# Whey_AGR_Sch.net
KiCad netlist of a schematic drawn in Altium Designer
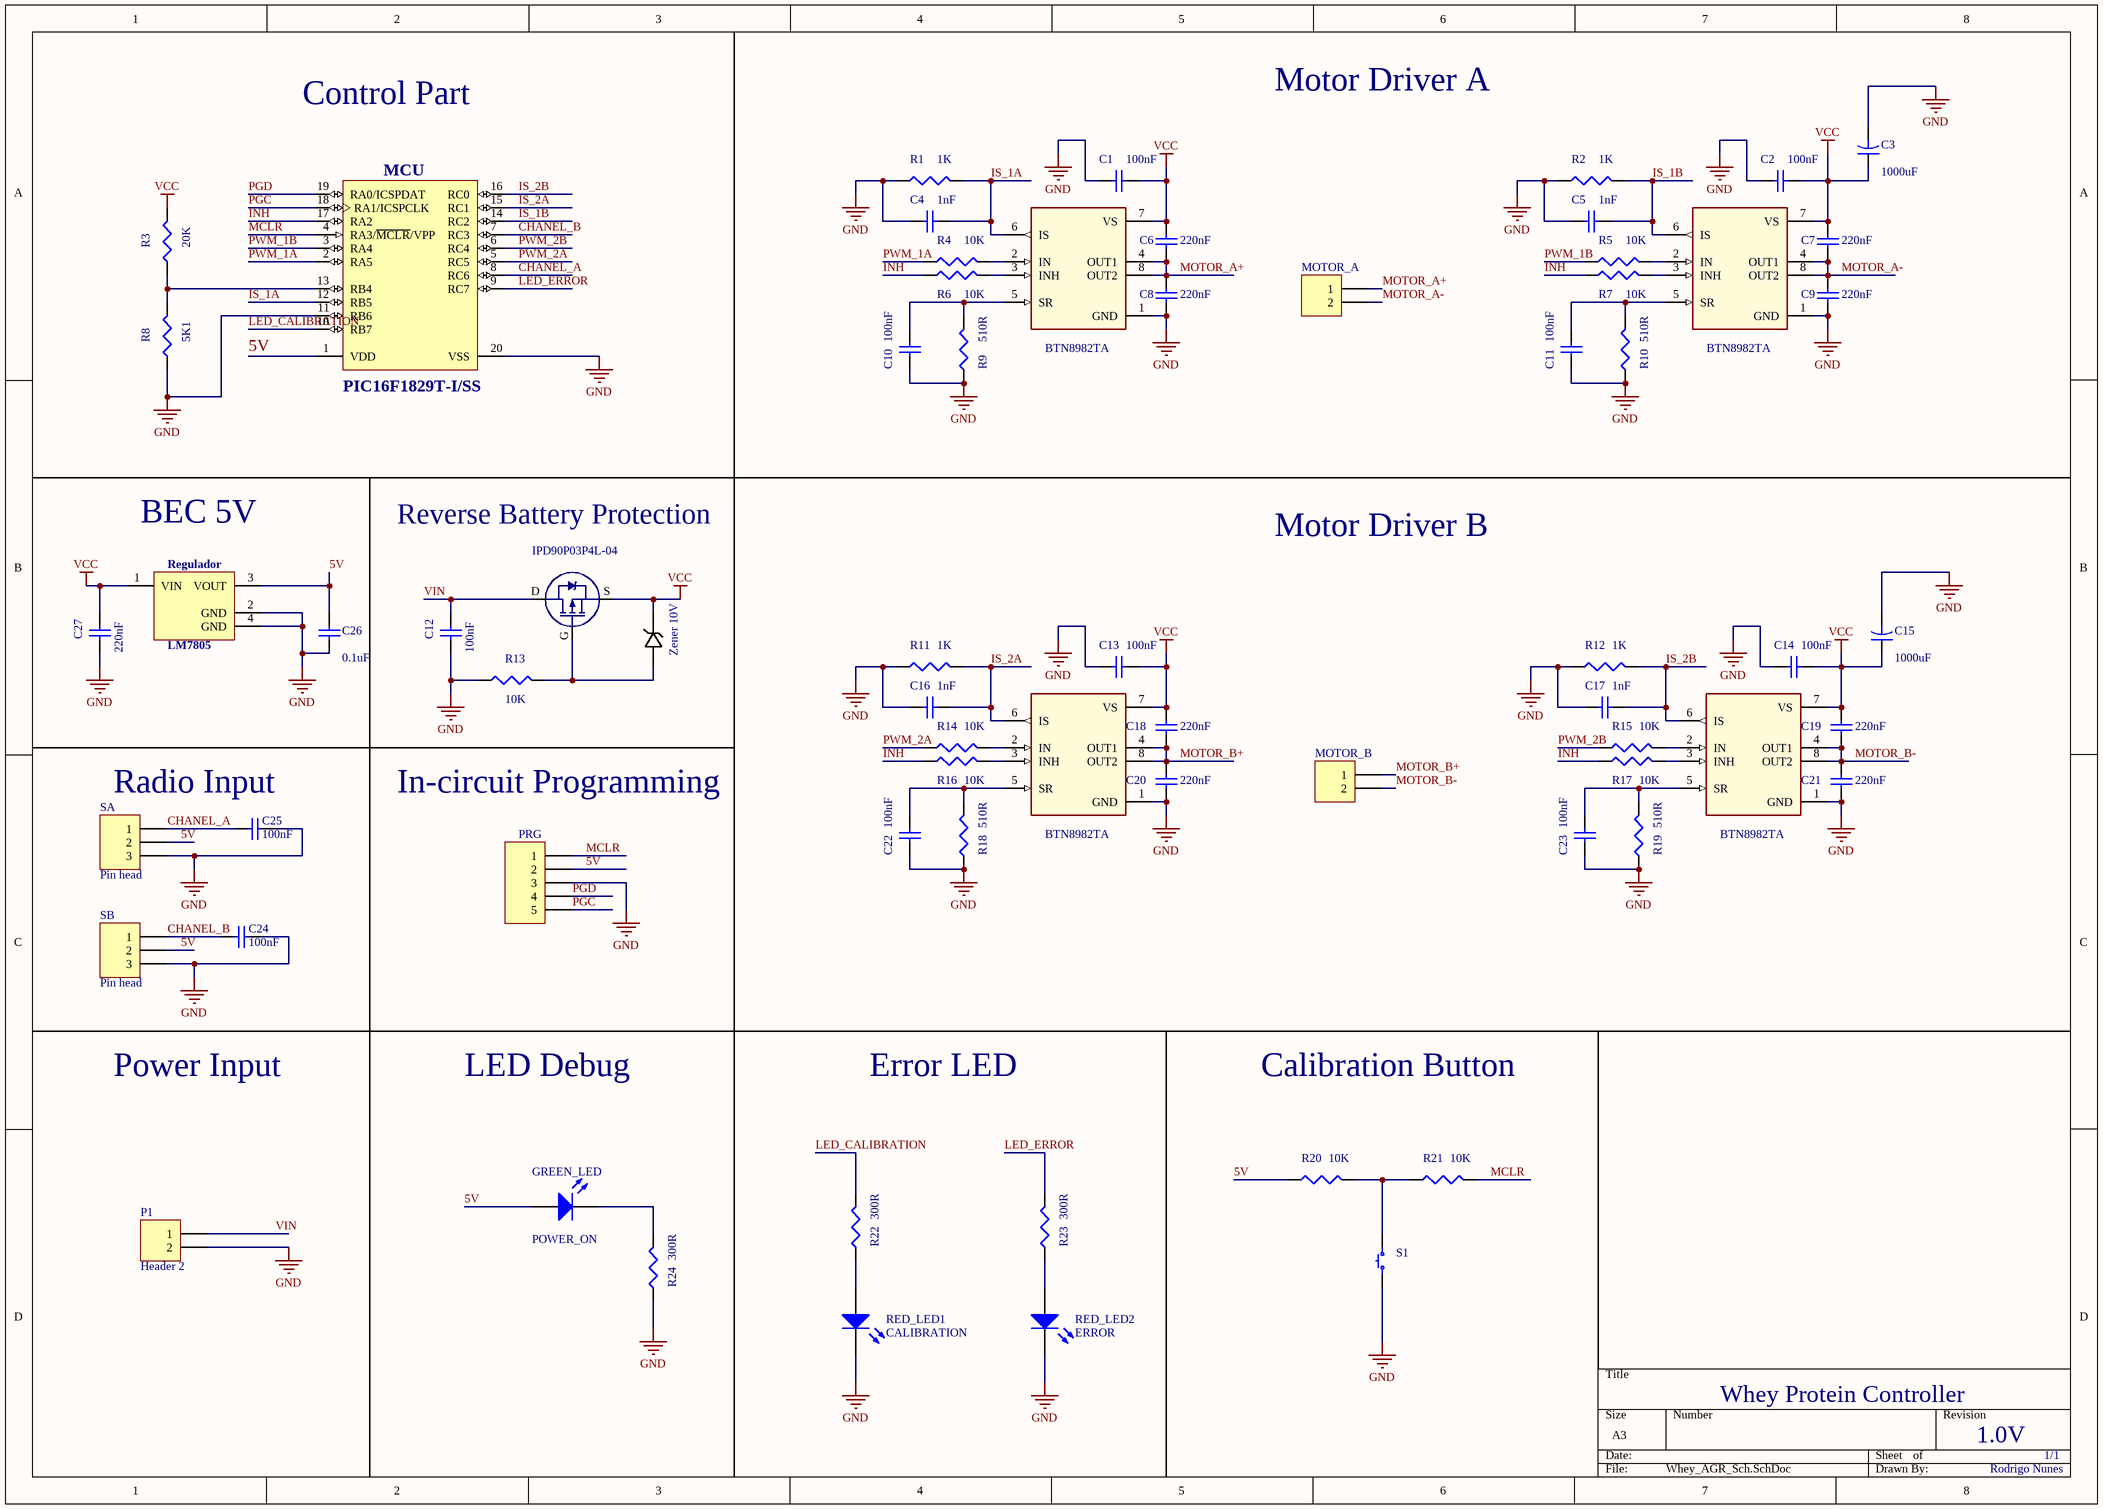
[diagram p0: Whey_AGR_Sch.SchDoc]

(export (version "E")
  (design (tool "Eeschema 10.0.6"))
  (components
    (comp (ref "C1")
      (value "100nF")
      (footprint "C1206")
      (description "Capacitor (Semiconductor SIM Model)")
      (fields (field (name "Comment") "Cap Semi") (field (name "PUBLISHER") "Altium Limited"))
      (libsource (lib "Miscellaneous Devices") (part "Cap Semi"))
    )
    (comp (ref "C2")
      (value "100nF")
      (footprint "C1206")
      (description "Capacitor (Semiconductor SIM Model)")
      (fields (field (name "Comment") "Cap Semi") (field (name "PUBLISHER") "Altium Limited"))
      (libsource (lib "Miscellaneous Devices") (part "Cap Semi"))
    )
    (comp (ref "C3")
      (value "1000uF")
      (footprint "CAPR5-4X5")
      (description "Capacitor")
      (fields (field (name "PUBLISHER") "Altium Limited"))
      (libsource (lib "Miscellaneous Devices") (part "Cap2"))
    )
    (comp (ref "C4")
      (value "1nF")
      (footprint "C1206")
      (description "Capacitor (Semiconductor SIM Model)")
      (fields (field (name "Comment") "Cap Semi") (field (name "PUBLISHER") "Altium Limited"))
      (libsource (lib "Miscellaneous Devices") (part "Cap Semi"))
    )
    (comp (ref "C5")
      (value "1nF")
      (footprint "C1206")
      (description "Capacitor (Semiconductor SIM Model)")
      (fields (field (name "Comment") "Cap Semi") (field (name "PUBLISHER") "Altium Limited"))
      (libsource (lib "Miscellaneous Devices") (part "Cap Semi"))
    )
    (comp (ref "C6")
      (value "220nF")
      (footprint "C1206")
      (description "Capacitor (Semiconductor SIM Model)")
      (fields (field (name "Comment") "Cap Semi") (field (name "PUBLISHER") "Altium Limited"))
      (libsource (lib "Miscellaneous Devices") (part "Cap Semi"))
    )
    (comp (ref "C7")
      (value "220nF")
      (footprint "C1206")
      (description "Capacitor (Semiconductor SIM Model)")
      (fields (field (name "Comment") "Cap Semi") (field (name "PUBLISHER") "Altium Limited"))
      (libsource (lib "Miscellaneous Devices") (part "Cap Semi"))
    )
    (comp (ref "C8")
      (value "220nF")
      (footprint "C1206")
      (description "Capacitor (Semiconductor SIM Model)")
      (fields (field (name "Comment") "Cap Semi") (field (name "PUBLISHER") "Altium Limited"))
      (libsource (lib "Miscellaneous Devices") (part "Cap Semi"))
    )
    (comp (ref "C9")
      (value "220nF")
      (footprint "C1206")
      (description "Capacitor (Semiconductor SIM Model)")
      (fields (field (name "Comment") "Cap Semi") (field (name "PUBLISHER") "Altium Limited"))
      (libsource (lib "Miscellaneous Devices") (part "Cap Semi"))
    )
    (comp (ref "C10")
      (value "100nF")
      (footprint "C1206")
      (description "Capacitor (Semiconductor SIM Model)")
      (fields (field (name "Comment") "Cap Semi") (field (name "PUBLISHER") "Altium Limited"))
      (libsource (lib "Miscellaneous Devices") (part "Cap Semi"))
    )
    (comp (ref "C11")
      (value "100nF")
      (footprint "C1206")
      (description "Capacitor (Semiconductor SIM Model)")
      (fields (field (name "Comment") "Cap Semi") (field (name "PUBLISHER") "Altium Limited"))
      (libsource (lib "Miscellaneous Devices") (part "Cap Semi"))
    )
    (comp (ref "C12")
      (value "100nF")
      (footprint "C1206")
      (description "Capacitor (Semiconductor SIM Model)")
      (fields (field (name "Comment") "Cap Semi") (field (name "PUBLISHER") "Altium Limited"))
      (libsource (lib "Miscellaneous Devices") (part "Cap Semi"))
    )
    (comp (ref "C13")
      (value "100nF")
      (footprint "C1206")
      (description "Capacitor (Semiconductor SIM Model)")
      (fields (field (name "Comment") "Cap Semi") (field (name "PUBLISHER") "Altium Limited"))
      (libsource (lib "Miscellaneous Devices") (part "Cap Semi"))
    )
    (comp (ref "C14")
      (value "100nF")
      (footprint "C1206")
      (description "Capacitor (Semiconductor SIM Model)")
      (fields (field (name "Comment") "Cap Semi") (field (name "PUBLISHER") "Altium Limited"))
      (libsource (lib "Miscellaneous Devices") (part "Cap Semi"))
    )
    (comp (ref "C15")
      (value "1000uF")
      (footprint "CAPR5-4X5")
      (description "Capacitor")
      (fields (field (name "Comment") "Cap2") (field (name "PUBLISHER") "Altium Limited"))
      (libsource (lib "Miscellaneous Devices") (part "Cap2"))
    )
    (comp (ref "C16")
      (value "1nF")
      (footprint "C1206")
      (description "Capacitor (Semiconductor SIM Model)")
      (fields (field (name "Comment") "Cap Semi") (field (name "PUBLISHER") "Altium Limited"))
      (libsource (lib "Miscellaneous Devices") (part "Cap Semi"))
    )
    (comp (ref "C17")
      (value "1nF")
      (footprint "C1206")
      (description "Capacitor (Semiconductor SIM Model)")
      (fields (field (name "Comment") "Cap Semi") (field (name "PUBLISHER") "Altium Limited"))
      (libsource (lib "Miscellaneous Devices") (part "Cap Semi"))
    )
    (comp (ref "C18")
      (value "220nF")
      (footprint "C1206")
      (description "Capacitor (Semiconductor SIM Model)")
      (fields (field (name "Comment") "Cap Semi") (field (name "PUBLISHER") "Altium Limited"))
      (libsource (lib "Miscellaneous Devices") (part "Cap Semi"))
    )
    (comp (ref "C19")
      (value "220nF")
      (footprint "C1206")
      (description "Capacitor (Semiconductor SIM Model)")
      (fields (field (name "Comment") "Cap Semi") (field (name "PUBLISHER") "Altium Limited"))
      (libsource (lib "Miscellaneous Devices") (part "Cap Semi"))
    )
    (comp (ref "C20")
      (value "220nF")
      (footprint "C1206")
      (description "Capacitor (Semiconductor SIM Model)")
      (fields (field (name "Comment") "Cap Semi") (field (name "PUBLISHER") "Altium Limited"))
      (libsource (lib "Miscellaneous Devices") (part "Cap Semi"))
    )
    (comp (ref "C21")
      (value "220nF")
      (footprint "C1206")
      (description "Capacitor (Semiconductor SIM Model)")
      (fields (field (name "Comment") "Cap Semi") (field (name "PUBLISHER") "Altium Limited"))
      (libsource (lib "Miscellaneous Devices") (part "Cap Semi"))
    )
    (comp (ref "C22")
      (value "100nF")
      (footprint "C1206")
      (description "Capacitor (Semiconductor SIM Model)")
      (fields (field (name "Comment") "Cap Semi") (field (name "PUBLISHER") "Altium Limited"))
      (libsource (lib "Miscellaneous Devices") (part "Cap Semi"))
    )
    (comp (ref "C23")
      (value "100nF")
      (footprint "C1206")
      (description "Capacitor (Semiconductor SIM Model)")
      (fields (field (name "Comment") "Cap Semi") (field (name "PUBLISHER") "Altium Limited"))
      (libsource (lib "Miscellaneous Devices") (part "Cap Semi"))
    )
    (comp (ref "C24")
      (value "100nF")
      (footprint "C1206")
      (description "Capacitor (Semiconductor SIM Model)")
      (fields (field (name "Comment") "Cap Semi") (field (name "PUBLISHER") "Altium Limited"))
      (libsource (lib "Miscellaneous Devices") (part "Cap Semi"))
    )
    (comp (ref "C25")
      (value "100nF")
      (footprint "C1206")
      (description "Capacitor (Semiconductor SIM Model)")
      (fields (field (name "Comment") "Cap Semi") (field (name "PUBLISHER") "Altium Limited"))
      (libsource (lib "Miscellaneous Devices") (part "Cap Semi"))
    )
    (comp (ref "C26")
      (value "0.1uF")
      (footprint "C1206")
      (description "Capacitor (Semiconductor SIM Model)")
      (fields (field (name "PUBLISHER") "Altium Limited"))
      (libsource (lib "Miscellaneous Devices") (part "Cap Semi"))
    )
    (comp (ref "C27")
      (value "220nF")
      (footprint "C1206")
      (description "Capacitor (Semiconductor SIM Model)")
      (fields (field (name "Comment") "Cap Semi") (field (name "PUBLISHER") "Altium Limited"))
      (libsource (lib "Miscellaneous Devices") (part "Cap Semi"))
    )
    (comp (ref "GREEN_LED")
      (value "POWER_ON")
      (footprint "3.2X1.6X1.1")
      (description "Typical RED, GREEN, YELLOW, AMBER GaAs LED")
      (fields (field (name "PUBLISHER") "Altium Limited"))
      (libsource (lib "Miscellaneous Devices") (part "LED2"))
    )
    (comp (ref "IPD90P03P4L-04")
      (value "IPD50P04P4")
      (footprint "TO-252")
      (description "MOSFET P-Ch -40V -50A DPAK-2 OptiMOS-P2")
      (libsource (lib "Components") (part "IPD50P04P4"))
    )
    (comp (ref "MCU")
      (value "PIC16F1829T-I/SS")
      (footprint "MCHP-SSOP-SS20_N")
      (fields (field (name "MANUFACTURER") "Microchip"))
      (libsource (lib "Microchip PIC16 Part 1") (part "PIC16F1829T-I/SS"))
    )
    (comp (ref "MOTOR_A")
      (value "Header 2")
      (footprint "HDR1X2")
      (description "Header, 2-Pin")
      (fields (field (name "PUBLISHER") "Altium Limited"))
      (libsource (lib "Miscellaneous Connectors") (part "Header 2"))
    )
    (comp (ref "MOTOR_B")
      (value "Header 2")
      (footprint "HDR1X2")
      (description "Header, 2-Pin")
      (fields (field (name "PUBLISHER") "Altium Limited"))
      (libsource (lib "Miscellaneous Connectors") (part "Header 2"))
    )
    (comp (ref "P1")
      (value "Header 2")
      (footprint "HDR1X2")
      (description "Header, 2-Pin")
      (fields (field (name "PUBLISHER") "Altium Limited"))
      (libsource (lib "Miscellaneous Connectors") (part "Header 2"))
    )
    (comp (ref "PRG")
      (value "Header 5")
      (footprint "HDR1X5")
      (description "Header, 5-Pin")
      (fields (field (name "PUBLISHER") "Altium Limited"))
      (libsource (lib "Miscellaneous Connectors") (part "Header 5"))
    )
    (comp (ref "R1")
      (value "1K")
      (footprint "J1-0603")
      (description "Resistor")
      (fields (field (name "Comment") "Res3") (field (name "PUBLISHER") "Altium Limited"))
      (libsource (lib "Miscellaneous Devices") (part "Res3"))
    )
    (comp (ref "R2")
      (value "1K")
      (footprint "J1-0603")
      (description "Resistor")
      (fields (field (name "Comment") "Res3") (field (name "PUBLISHER") "Altium Limited"))
      (libsource (lib "Miscellaneous Devices") (part "Res3"))
    )
    (comp (ref "R3")
      (value "20K")
      (footprint "J1-0603")
      (description "Resistor_SMD")
      (fields (field (name "Comment") "Res3") (field (name "PUBLISHER") "Altium Limited"))
      (libsource (lib "Miscellaneous Devices") (part "Res3"))
    )
    (comp (ref "R4")
      (value "10K")
      (footprint "J1-0603")
      (description "Resistor")
      (fields (field (name "Comment") "Res3") (field (name "PUBLISHER") "Altium Limited"))
      (libsource (lib "Miscellaneous Devices") (part "Res3"))
    )
    (comp (ref "R5")
      (value "10K")
      (footprint "J1-0603")
      (description "Resistor")
      (fields (field (name "Comment") "Res3") (field (name "PUBLISHER") "Altium Limited"))
      (libsource (lib "Miscellaneous Devices") (part "Res3"))
    )
    (comp (ref "R6")
      (value "10K")
      (footprint "J1-0603")
      (description "Resistor")
      (fields (field (name "Comment") "Res3") (field (name "PUBLISHER") "Altium Limited"))
      (libsource (lib "Miscellaneous Devices") (part "Res3"))
    )
    (comp (ref "R7")
      (value "10K")
      (footprint "J1-0603")
      (description "Resistor")
      (fields (field (name "Comment") "Res3") (field (name "PUBLISHER") "Altium Limited"))
      (libsource (lib "Miscellaneous Devices") (part "Res3"))
    )
    (comp (ref "R8")
      (value "5K1")
      (footprint "J1-0603")
      (description "Resistor_SMD")
      (fields (field (name "Comment") "Res3") (field (name "PUBLISHER") "Altium Limited"))
      (libsource (lib "Miscellaneous Devices") (part "Res3"))
    )
    (comp (ref "R9")
      (value "510R")
      (footprint "J1-0603")
      (description "Resistor_SMD")
      (fields (field (name "Comment") "Res3") (field (name "PUBLISHER") "Altium Limited"))
      (libsource (lib "Miscellaneous Devices") (part "Res3"))
    )
    (comp (ref "R10")
      (value "510R")
      (footprint "J1-0603")
      (description "Resistor_SMD")
      (fields (field (name "Comment") "Res3") (field (name "PUBLISHER") "Altium Limited"))
      (libsource (lib "Miscellaneous Devices") (part "Res3"))
    )
    (comp (ref "R11")
      (value "1K")
      (footprint "J1-0603")
      (description "Resistor")
      (fields (field (name "Comment") "Res3") (field (name "PUBLISHER") "Altium Limited"))
      (libsource (lib "Miscellaneous Devices") (part "Res3"))
    )
    (comp (ref "R12")
      (value "1K")
      (footprint "J1-0603")
      (description "Resistor")
      (fields (field (name "Comment") "Res3") (field (name "PUBLISHER") "Altium Limited"))
      (libsource (lib "Miscellaneous Devices") (part "Res3"))
    )
    (comp (ref "R13")
      (value "10K")
      (footprint "J1-0603")
      (description "Resistor")
      (fields (field (name "Comment") "Res3") (field (name "PUBLISHER") "Altium Limited"))
      (libsource (lib "Miscellaneous Devices") (part "Res3"))
    )
    (comp (ref "R14")
      (value "10K")
      (footprint "J1-0603")
      (description "Resistor")
      (fields (field (name "Comment") "Res3") (field (name "PUBLISHER") "Altium Limited"))
      (libsource (lib "Miscellaneous Devices") (part "Res3"))
    )
    (comp (ref "R15")
      (value "10K")
      (footprint "J1-0603")
      (description "Resistor")
      (fields (field (name "Comment") "Res3") (field (name "PUBLISHER") "Altium Limited"))
      (libsource (lib "Miscellaneous Devices") (part "Res3"))
    )
    (comp (ref "R16")
      (value "10K")
      (footprint "J1-0603")
      (description "Resistor")
      (fields (field (name "Comment") "Res3") (field (name "PUBLISHER") "Altium Limited"))
      (libsource (lib "Miscellaneous Devices") (part "Res3"))
    )
    (comp (ref "R17")
      (value "10K")
      (footprint "J1-0603")
      (description "Resistor")
      (fields (field (name "Comment") "Res3") (field (name "PUBLISHER") "Altium Limited"))
      (libsource (lib "Miscellaneous Devices") (part "Res3"))
    )
    (comp (ref "R18")
      (value "510R")
      (footprint "J1-0603")
      (description "Resistor_SMD")
      (fields (field (name "Comment") "Res3") (field (name "PUBLISHER") "Altium Limited"))
      (libsource (lib "Miscellaneous Devices") (part "Res3"))
    )
    (comp (ref "R19")
      (value "510R")
      (footprint "J1-0603")
      (description "Resistor_SMD")
      (fields (field (name "Comment") "Res3") (field (name "PUBLISHER") "Altium Limited"))
      (libsource (lib "Miscellaneous Devices") (part "Res3"))
    )
    (comp (ref "R20")
      (value "10K")
      (footprint "J1-0603")
      (description "Resistor")
      (fields (field (name "Comment") "Res3") (field (name "PUBLISHER") "Altium Limited"))
      (libsource (lib "Miscellaneous Devices") (part "Res3"))
    )
    (comp (ref "R21")
      (value "10K")
      (footprint "J1-0603")
      (description "Resistor")
      (fields (field (name "Comment") "Res3") (field (name "PUBLISHER") "Altium Limited"))
      (libsource (lib "Miscellaneous Devices") (part "Res3"))
    )
    (comp (ref "R22")
      (value "300R")
      (footprint "J1-0603")
      (description "Resistor_SMD")
      (fields (field (name "Comment") "Res3") (field (name "PUBLISHER") "Altium Limited"))
      (libsource (lib "Miscellaneous Devices") (part "Res3"))
    )
    (comp (ref "R23")
      (value "300R")
      (footprint "J1-0603")
      (description "Resistor_SMD")
      (fields (field (name "Comment") "Res3") (field (name "PUBLISHER") "Altium Limited"))
      (libsource (lib "Miscellaneous Devices") (part "Res3"))
    )
    (comp (ref "R24")
      (value "300R")
      (footprint "J1-0603")
      (description "Resistor_SMD")
      (fields (field (name "Comment") "Res3") (field (name "PUBLISHER") "Altium Limited"))
      (libsource (lib "Miscellaneous Devices") (part "Res3"))
    )
    (comp (ref "RED_LED1")
      (value "CALIBRATION")
      (footprint "3.2X1.6X1.1")
      (description "Typical RED, GREEN, YELLOW, AMBER GaAs LED")
      (fields (field (name "PUBLISHER") "Altium Limited"))
      (libsource (lib "Miscellaneous Devices") (part "LED2"))
    )
    (comp (ref "RED_LED2")
      (value "ERROR")
      (footprint "3.2X1.6X1.1")
      (description "Typical RED, GREEN, YELLOW, AMBER GaAs LED")
      (fields (field (name "PUBLISHER") "Altium Limited"))
      (libsource (lib "Miscellaneous Devices") (part "LED2"))
    )
    (comp (ref "Regulador")
      (value "LM7805")
      (footprint "SOT223")
      (description "5V Regulator, 3-Pin SOT-223, Extended Temperature, Tape and Reel")
      (fields (field (name "PUBLISHER") "Altium Limited"))
      (libsource (lib "Components") (part "LM7805MP/NOPB"))
    )
    (comp (ref "S1")
      (value "FSMSMTR")
      (footprint "TE FSMSMTR")
      (description "SWITCH TACTILE SPST-NO 0.05A 24V")
      (fields (field (name "MANUFACTURER") "TE Connectivity Alcoswitch Switches"))
      (libsource (lib "Button - Tactile") (part "FSMSMTR"))
    )
    (comp (ref "SA")
      (value "Pin head")
      (footprint "HDR1X3")
      (description "Header, 3-Pin")
      (fields (field (name "PUBLISHER") "Altium Limited"))
      (libsource (lib "Miscellaneous Connectors") (part "Header 3"))
    )
    (comp (ref "SB")
      (value "Pin head")
      (footprint "HDR1X3")
      (description "Header, 3-Pin")
      (fields (field (name "PUBLISHER") "Altium Limited"))
      (libsource (lib "Miscellaneous Connectors") (part "Header 3"))
    )
    (comp (ref "U1")
      (value "BTN8982TA")
      (footprint "TO127P1500X440-8N-1")
      (description "High Current PN Half Bridge NovalithIC")
      (fields (field (name "MANUFACTURER") "Infineon Technologies"))
      (libsource (lib "BTN8982TA") (part "BTN8982TA"))
    )
    (comp (ref "U2")
      (value "BTN8982TA")
      (footprint "TO127P1500X440-8N-1")
      (description "High Current PN Half Bridge NovalithIC")
      (fields (field (name "MANUFACTURER") "Infineon Technologies"))
      (libsource (lib "BTN8982TA") (part "BTN8982TA"))
    )
    (comp (ref "U3")
      (value "BTN8982TA")
      (footprint "TO127P1500X440-8N-1")
      (description "High Current PN Half Bridge NovalithIC")
      (fields (field (name "MANUFACTURER") "Infineon Technologies"))
      (libsource (lib "BTN8982TA") (part "BTN8982TA"))
    )
    (comp (ref "U4")
      (value "BTN8982TA")
      (footprint "TO127P1500X440-8N-1")
      (description "High Current PN Half Bridge NovalithIC")
      (fields (field (name "MANUFACTURER") "Infineon Technologies"))
      (libsource (lib "BTN8982TA") (part "BTN8982TA"))
    )
    (comp (ref "Zener 10V")
      (value "BZT52HC10WF-7")
      (footprint "SOD123")
      (description "Diode Zener 10.6V 375 mW AEC-Q101")
      (libsource (lib "Components") (part "BZT52HC10WF-7"))
    )
  )
  (nets
    (net (code "1") (name "/5V") (class "Default")
      (node (ref "C26") (pin "1") (pinfunction "1_1") (pintype "passive"))
      (node (ref "GREEN_LED") (pin "1") (pinfunction "A_1") (pintype "passive"))
      (node (ref "MCU") (pin "1") (pinfunction "VDD_1") (pintype "power_in"))
      (node (ref "PRG") (pin "2") (pinfunction "2_2") (pintype "passive"))
      (node (ref "R20") (pin "1") (pinfunction "1_1") (pintype "passive"))
      (node (ref "Regulador") (pin "3") (pinfunction "VOUT_3") (pintype "power_in"))
      (node (ref "SA") (pin "2") (pinfunction "2_2") (pintype "passive"))
      (node (ref "SB") (pin "2") (pinfunction "2_2") (pintype "passive"))
    )
    (net (code "2") (name "/CHANEL_A") (class "Default")
      (node (ref "C25") (pin "1") (pinfunction "1_1") (pintype "passive"))
      (node (ref "MCU") (pin "8") (pinfunction "RC6_8") (pintype "bidirectional"))
      (node (ref "SA") (pin "1") (pinfunction "1_1") (pintype "passive"))
    )
    (net (code "3") (name "/CHANEL_B") (class "Default")
      (node (ref "C24") (pin "2") (pinfunction "2_2") (pintype "passive"))
      (node (ref "MCU") (pin "7") (pinfunction "RC3_7") (pintype "bidirectional"))
      (node (ref "SB") (pin "1") (pinfunction "1_1") (pintype "passive"))
    )
    (net (code "4") (name "/INH") (class "Default")
      (node (ref "MCU") (pin "17") (pinfunction "RA2_17") (pintype "bidirectional"))
      (node (ref "R16") (pin "1") (pinfunction "1_1") (pintype "passive"))
      (node (ref "R17") (pin "1") (pinfunction "1_1") (pintype "passive"))
      (node (ref "R6") (pin "1") (pinfunction "1_1") (pintype "passive"))
      (node (ref "R7") (pin "1") (pinfunction "1_1") (pintype "passive"))
    )
    (net (code "5") (name "/IS_1A") (class "Default")
      (node (ref "C4") (pin "2") (pinfunction "2_2") (pintype "passive"))
      (node (ref "MCU") (pin "12") (pinfunction "RB5_12") (pintype "bidirectional"))
      (node (ref "R1") (pin "2") (pinfunction "2_2") (pintype "passive"))
      (node (ref "U1") (pin "6") (pinfunction "IS_6") (pintype "output"))
    )
    (net (code "6") (name "/IS_1B") (class "Default")
      (node (ref "C5") (pin "2") (pinfunction "2_2") (pintype "passive"))
      (node (ref "MCU") (pin "14") (pinfunction "RC2_14") (pintype "bidirectional"))
      (node (ref "R2") (pin "2") (pinfunction "2_2") (pintype "passive"))
      (node (ref "U2") (pin "6") (pinfunction "IS_6") (pintype "output"))
    )
    (net (code "7") (name "/IS_2A") (class "Default")
      (node (ref "C16") (pin "2") (pinfunction "2_2") (pintype "passive"))
      (node (ref "MCU") (pin "15") (pinfunction "RC1_15") (pintype "bidirectional"))
      (node (ref "R11") (pin "2") (pinfunction "2_2") (pintype "passive"))
      (node (ref "U3") (pin "6") (pinfunction "IS_6") (pintype "output"))
    )
    (net (code "8") (name "/IS_2B") (class "Default")
      (node (ref "C17") (pin "2") (pinfunction "2_2") (pintype "passive"))
      (node (ref "MCU") (pin "16") (pinfunction "RC0_16") (pintype "bidirectional"))
      (node (ref "R12") (pin "2") (pinfunction "2_2") (pintype "passive"))
      (node (ref "U4") (pin "6") (pinfunction "IS_6") (pintype "output"))
    )
    (net (code "9") (name "/LED_CALIBRATION") (class "Default")
      (node (ref "MCU") (pin "10") (pinfunction "RB7_10") (pintype "bidirectional"))
      (node (ref "R22") (pin "2") (pinfunction "2_2") (pintype "passive"))
    )
    (net (code "10") (name "/LED_ERROR") (class "Default")
      (node (ref "MCU") (pin "9") (pinfunction "RC7_9") (pintype "bidirectional"))
      (node (ref "R23") (pin "2") (pinfunction "2_2") (pintype "passive"))
    )
    (net (code "11") (name "/MCLR") (class "Default")
      (node (ref "MCU") (pin "4") (pinfunction "RA3/~{MCLR}/VPP_4") (pintype "input"))
      (node (ref "PRG") (pin "1") (pinfunction "1_1") (pintype "passive"))
      (node (ref "R21") (pin "2") (pinfunction "2_2") (pintype "passive"))
    )
    (net (code "12") (name "/MOTOR_A+") (class "Default")
      (node (ref "C6") (pin "1") (pinfunction "1_1") (pintype "passive"))
      (node (ref "C8") (pin "2") (pinfunction "2_2") (pintype "passive"))
      (node (ref "MOTOR_A") (pin "1") (pinfunction "1_1") (pintype "passive"))
      (node (ref "U1") (pin "4") (pinfunction "OUT1_4") (pintype "passive"))
      (node (ref "U1") (pin "8") (pinfunction "OUT2_8") (pintype "passive"))
    )
    (net (code "13") (name "/MOTOR_A-") (class "Default")
      (node (ref "C7") (pin "1") (pinfunction "1_1") (pintype "passive"))
      (node (ref "C9") (pin "2") (pinfunction "2_2") (pintype "passive"))
      (node (ref "MOTOR_A") (pin "2") (pinfunction "2_2") (pintype "passive"))
      (node (ref "U2") (pin "4") (pinfunction "OUT1_4") (pintype "passive"))
      (node (ref "U2") (pin "8") (pinfunction "OUT2_8") (pintype "passive"))
    )
    (net (code "14") (name "/MOTOR_B+") (class "Default")
      (node (ref "C18") (pin "1") (pinfunction "1_1") (pintype "passive"))
      (node (ref "C20") (pin "2") (pinfunction "2_2") (pintype "passive"))
      (node (ref "MOTOR_B") (pin "1") (pinfunction "1_1") (pintype "passive"))
      (node (ref "U3") (pin "4") (pinfunction "OUT1_4") (pintype "passive"))
      (node (ref "U3") (pin "8") (pinfunction "OUT2_8") (pintype "passive"))
    )
    (net (code "15") (name "/MOTOR_B-") (class "Default")
      (node (ref "C19") (pin "1") (pinfunction "1_1") (pintype "passive"))
      (node (ref "C21") (pin "2") (pinfunction "2_2") (pintype "passive"))
      (node (ref "MOTOR_B") (pin "2") (pinfunction "2_2") (pintype "passive"))
      (node (ref "U4") (pin "4") (pinfunction "OUT1_4") (pintype "passive"))
      (node (ref "U4") (pin "8") (pinfunction "OUT2_8") (pintype "passive"))
    )
    (net (code "16") (name "/PGC") (class "Default")
      (node (ref "MCU") (pin "18") (pinfunction "RA1/ICSPCLK_18") (pintype "bidirectional"))
      (node (ref "PRG") (pin "5") (pinfunction "5_5") (pintype "passive"))
    )
    (net (code "17") (name "/PGD") (class "Default")
      (node (ref "MCU") (pin "19") (pinfunction "RA0/ICSPDAT_19") (pintype "bidirectional"))
      (node (ref "PRG") (pin "4") (pinfunction "4_4") (pintype "passive"))
    )
    (net (code "18") (name "/PWM_1A") (class "Default")
      (node (ref "MCU") (pin "2") (pinfunction "RA5_2") (pintype "bidirectional"))
      (node (ref "R4") (pin "1") (pinfunction "1_1") (pintype "passive"))
    )
    (net (code "19") (name "/PWM_1B") (class "Default")
      (node (ref "MCU") (pin "3") (pinfunction "RA4_3") (pintype "bidirectional"))
      (node (ref "R5") (pin "1") (pinfunction "1_1") (pintype "passive"))
    )
    (net (code "20") (name "/PWM_2A") (class "Default")
      (node (ref "MCU") (pin "5") (pinfunction "RC5_5") (pintype "bidirectional"))
      (node (ref "R14") (pin "1") (pinfunction "1_1") (pintype "passive"))
    )
    (net (code "21") (name "/PWM_2B") (class "Default")
      (node (ref "MCU") (pin "6") (pinfunction "RC4_6") (pintype "bidirectional"))
      (node (ref "R15") (pin "1") (pinfunction "1_1") (pintype "passive"))
    )
    (net (code "22") (name "/VIN") (class "Default")
      (node (ref "C12") (pin "2") (pinfunction "2_2") (pintype "passive"))
      (node (ref "IPD90P03P4L-04") (pin "D") (pintype "passive"))
      (node (ref "P1") (pin "1") (pinfunction "1_1") (pintype "passive"))
    )
    (net (code "23") (name "GND") (class "Default")
      (node (ref "C1") (pin "1") (pinfunction "1_1") (pintype "passive"))
      (node (ref "C10") (pin "1") (pinfunction "1_1") (pintype "passive"))
      (node (ref "C11") (pin "1") (pinfunction "1_1") (pintype "passive"))
      (node (ref "C12") (pin "1") (pinfunction "1_1") (pintype "passive"))
      (node (ref "C13") (pin "1") (pinfunction "1_1") (pintype "passive"))
      (node (ref "C14") (pin "1") (pinfunction "1_1") (pintype "passive"))
      (node (ref "C15") (pin "2") (pinfunction "2_2") (pintype "passive"))
      (node (ref "C16") (pin "1") (pinfunction "1_1") (pintype "passive"))
      (node (ref "C17") (pin "1") (pinfunction "1_1") (pintype "passive"))
      (node (ref "C2") (pin "1") (pinfunction "1_1") (pintype "passive"))
      (node (ref "C20") (pin "1") (pinfunction "1_1") (pintype "passive"))
      (node (ref "C21") (pin "1") (pinfunction "1_1") (pintype "passive"))
      (node (ref "C22") (pin "1") (pinfunction "1_1") (pintype "passive"))
      (node (ref "C23") (pin "1") (pinfunction "1_1") (pintype "passive"))
      (node (ref "C24") (pin "1") (pinfunction "1_1") (pintype "passive"))
      (node (ref "C25") (pin "2") (pinfunction "2_2") (pintype "passive"))
      (node (ref "C26") (pin "2") (pinfunction "2_2") (pintype "passive"))
      (node (ref "C27") (pin "1") (pinfunction "1_1") (pintype "passive"))
      (node (ref "C3") (pin "2") (pinfunction "2_2") (pintype "passive"))
      (node (ref "C4") (pin "1") (pinfunction "1_1") (pintype "passive"))
      (node (ref "C5") (pin "1") (pinfunction "1_1") (pintype "passive"))
      (node (ref "C8") (pin "1") (pinfunction "1_1") (pintype "passive"))
      (node (ref "C9") (pin "1") (pinfunction "1_1") (pintype "passive"))
      (node (ref "MCU") (pin "11") (pinfunction "RB6_11") (pintype "bidirectional"))
      (node (ref "MCU") (pin "20") (pinfunction "VSS_20") (pintype "power_in"))
      (node (ref "P1") (pin "2") (pinfunction "2_2") (pintype "passive"))
      (node (ref "PRG") (pin "3") (pinfunction "3_3") (pintype "passive"))
      (node (ref "R1") (pin "1") (pinfunction "1_1") (pintype "passive"))
      (node (ref "R10") (pin "1") (pinfunction "1_1") (pintype "passive"))
      (node (ref "R11") (pin "1") (pinfunction "1_1") (pintype "passive"))
      (node (ref "R12") (pin "1") (pinfunction "1_1") (pintype "passive"))
      (node (ref "R13") (pin "1") (pinfunction "1_1") (pintype "passive"))
      (node (ref "R18") (pin "1") (pinfunction "1_1") (pintype "passive"))
      (node (ref "R19") (pin "1") (pinfunction "1_1") (pintype "passive"))
      (node (ref "R2") (pin "1") (pinfunction "1_1") (pintype "passive"))
      (node (ref "R24") (pin "1") (pinfunction "1_1") (pintype "passive"))
      (node (ref "R8") (pin "1") (pinfunction "1_1") (pintype "passive"))
      (node (ref "R9") (pin "1") (pinfunction "1_1") (pintype "passive"))
      (node (ref "RED_LED1") (pin "2") (pinfunction "K_2") (pintype "passive"))
      (node (ref "RED_LED2") (pin "2") (pinfunction "K_2") (pintype "passive"))
      (node (ref "Regulador") (pin "2") (pinfunction "GND_2") (pintype "power_in"))
      (node (ref "Regulador") (pin "4") (pinfunction "GND_4") (pintype "power_in"))
      (node (ref "S1") (pin "1") (pinfunction "1_1") (pintype "passive"))
      (node (ref "SA") (pin "3") (pinfunction "3_3") (pintype "passive"))
      (node (ref "SB") (pin "3") (pinfunction "3_3") (pintype "passive"))
      (node (ref "U1") (pin "1") (pinfunction "GND_1") (pintype "power_in"))
      (node (ref "U2") (pin "1") (pinfunction "GND_1") (pintype "power_in"))
      (node (ref "U3") (pin "1") (pinfunction "GND_1") (pintype "power_in"))
      (node (ref "U4") (pin "1") (pinfunction "GND_1") (pintype "power_in"))
    )
    (net (code "24") (name "Net-(GREEN_LED-K)") (class "Default")
      (node (ref "GREEN_LED") (pin "2") (pinfunction "K_2") (pintype "passive"))
      (node (ref "R24") (pin "2") (pinfunction "2_2") (pintype "passive"))
    )
    (net (code "25") (name "Net-(IPD90P03P4L-04-PadG)") (class "Default")
      (node (ref "IPD90P03P4L-04") (pin "G") (pintype "passive"))
      (node (ref "R13") (pin "2") (pinfunction "2_2") (pintype "passive"))
      (node (ref "Zener 10V") (pin "A") (pinfunction "A_A") (pintype "passive"))
    )
    (net (code "26") (name "Net-(MCU-RB4)") (class "Default")
      (node (ref "MCU") (pin "13") (pinfunction "RB4_13") (pintype "bidirectional"))
      (node (ref "R3") (pin "1") (pinfunction "1_1") (pintype "passive"))
      (node (ref "R8") (pin "2") (pinfunction "2_2") (pintype "passive"))
    )
    (net (code "27") (name "Net-(R20-Pad2)") (class "Default")
      (node (ref "R20") (pin "2") (pinfunction "2_2") (pintype "passive"))
      (node (ref "R21") (pin "1") (pinfunction "1_1") (pintype "passive"))
      (node (ref "S1") (pin "2") (pinfunction "2_2") (pintype "passive"))
    )
    (net (code "28") (name "Net-(RED_LED1-A)") (class "Default")
      (node (ref "R22") (pin "1") (pinfunction "1_1") (pintype "passive"))
      (node (ref "RED_LED1") (pin "1") (pinfunction "A_1") (pintype "passive"))
    )
    (net (code "29") (name "Net-(RED_LED2-A)") (class "Default")
      (node (ref "R23") (pin "1") (pinfunction "1_1") (pintype "passive"))
      (node (ref "RED_LED2") (pin "1") (pinfunction "A_1") (pintype "passive"))
    )
    (net (code "30") (name "Net-(U1-IN)") (class "Default")
      (node (ref "R4") (pin "2") (pinfunction "2_2") (pintype "passive"))
      (node (ref "U1") (pin "2") (pinfunction "IN_2") (pintype "input"))
    )
    (net (code "31") (name "Net-(U1-INH)") (class "Default")
      (node (ref "R6") (pin "2") (pinfunction "2_2") (pintype "passive"))
      (node (ref "U1") (pin "3") (pinfunction "INH_3") (pintype "input"))
    )
    (net (code "32") (name "Net-(U1-SR)") (class "Default")
      (node (ref "C10") (pin "2") (pinfunction "2_2") (pintype "passive"))
      (node (ref "R9") (pin "2") (pinfunction "2_2") (pintype "passive"))
      (node (ref "U1") (pin "5") (pinfunction "SR_5") (pintype "input"))
    )
    (net (code "33") (name "Net-(U2-IN)") (class "Default")
      (node (ref "R5") (pin "2") (pinfunction "2_2") (pintype "passive"))
      (node (ref "U2") (pin "2") (pinfunction "IN_2") (pintype "input"))
    )
    (net (code "34") (name "Net-(U2-INH)") (class "Default")
      (node (ref "R7") (pin "2") (pinfunction "2_2") (pintype "passive"))
      (node (ref "U2") (pin "3") (pinfunction "INH_3") (pintype "input"))
    )
    (net (code "35") (name "Net-(U2-SR)") (class "Default")
      (node (ref "C11") (pin "2") (pinfunction "2_2") (pintype "passive"))
      (node (ref "R10") (pin "2") (pinfunction "2_2") (pintype "passive"))
      (node (ref "U2") (pin "5") (pinfunction "SR_5") (pintype "input"))
    )
    (net (code "36") (name "Net-(U3-IN)") (class "Default")
      (node (ref "R14") (pin "2") (pinfunction "2_2") (pintype "passive"))
      (node (ref "U3") (pin "2") (pinfunction "IN_2") (pintype "input"))
    )
    (net (code "37") (name "Net-(U3-INH)") (class "Default")
      (node (ref "R16") (pin "2") (pinfunction "2_2") (pintype "passive"))
      (node (ref "U3") (pin "3") (pinfunction "INH_3") (pintype "input"))
    )
    (net (code "38") (name "Net-(U3-SR)") (class "Default")
      (node (ref "C22") (pin "2") (pinfunction "2_2") (pintype "passive"))
      (node (ref "R18") (pin "2") (pinfunction "2_2") (pintype "passive"))
      (node (ref "U3") (pin "5") (pinfunction "SR_5") (pintype "input"))
    )
    (net (code "39") (name "Net-(U4-IN)") (class "Default")
      (node (ref "R15") (pin "2") (pinfunction "2_2") (pintype "passive"))
      (node (ref "U4") (pin "2") (pinfunction "IN_2") (pintype "input"))
    )
    (net (code "40") (name "Net-(U4-INH)") (class "Default")
      (node (ref "R17") (pin "2") (pinfunction "2_2") (pintype "passive"))
      (node (ref "U4") (pin "3") (pinfunction "INH_3") (pintype "input"))
    )
    (net (code "41") (name "Net-(U4-SR)") (class "Default")
      (node (ref "C23") (pin "2") (pinfunction "2_2") (pintype "passive"))
      (node (ref "R19") (pin "2") (pinfunction "2_2") (pintype "passive"))
      (node (ref "U4") (pin "5") (pinfunction "SR_5") (pintype "input"))
    )
    (net (code "42") (name "VCC") (class "Default")
      (node (ref "C1") (pin "2") (pinfunction "2_2") (pintype "passive"))
      (node (ref "C13") (pin "2") (pinfunction "2_2") (pintype "passive"))
      (node (ref "C14") (pin "2") (pinfunction "2_2") (pintype "passive"))
      (node (ref "C15") (pin "1") (pinfunction "1_1") (pintype "passive"))
      (node (ref "C18") (pin "2") (pinfunction "2_2") (pintype "passive"))
      (node (ref "C19") (pin "2") (pinfunction "2_2") (pintype "passive"))
      (node (ref "C2") (pin "2") (pinfunction "2_2") (pintype "passive"))
      (node (ref "C27") (pin "2") (pinfunction "2_2") (pintype "passive"))
      (node (ref "C3") (pin "1") (pinfunction "1_1") (pintype "passive"))
      (node (ref "C6") (pin "2") (pinfunction "2_2") (pintype "passive"))
      (node (ref "C7") (pin "2") (pinfunction "2_2") (pintype "passive"))
      (node (ref "IPD90P03P4L-04") (pin "S") (pintype "passive"))
      (node (ref "R3") (pin "2") (pinfunction "2_2") (pintype "passive"))
      (node (ref "Regulador") (pin "1") (pinfunction "VIN_1") (pintype "power_in"))
      (node (ref "U1") (pin "7") (pinfunction "VS_7") (pintype "power_in"))
      (node (ref "U2") (pin "7") (pinfunction "VS_7") (pintype "power_in"))
      (node (ref "U3") (pin "7") (pinfunction "VS_7") (pintype "power_in"))
      (node (ref "U4") (pin "7") (pinfunction "VS_7") (pintype "power_in"))
      (node (ref "Zener 10V") (pin "K") (pinfunction "K_K") (pintype "passive"))
    )
  )
)
